# PN532.net
KiCad netlist of a schematic drawn in Altium Designer
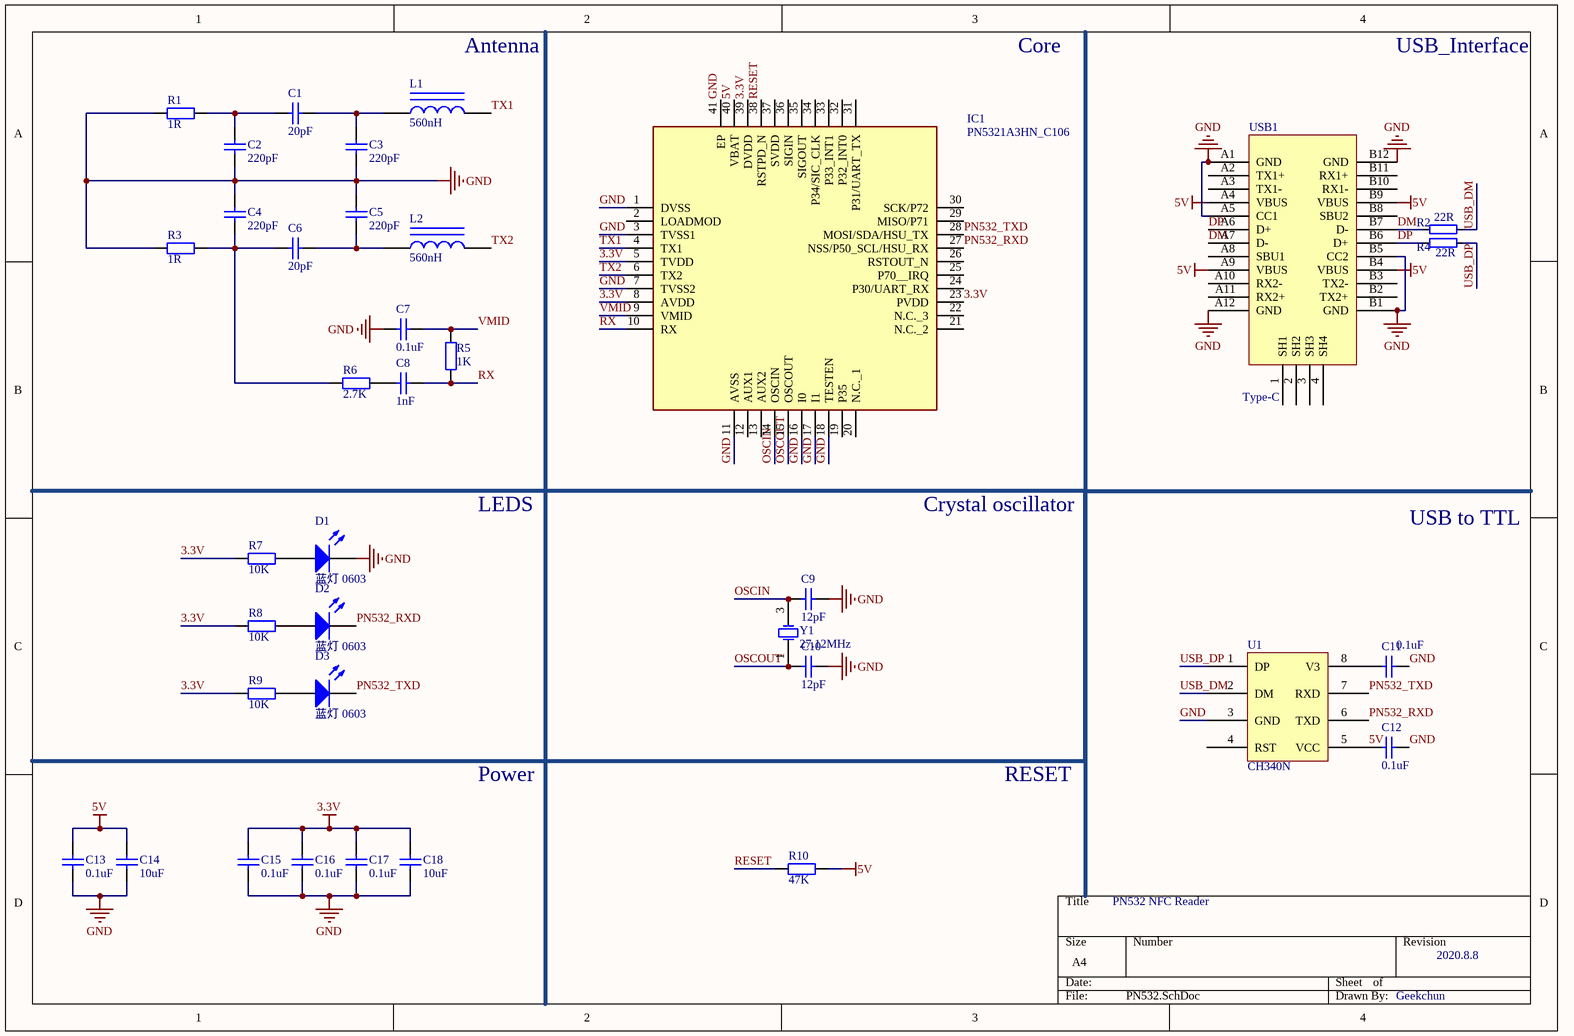
[diagram p0: PN532.SchDoc]

(export (version "E")
  (design (tool "Eeschema 10.0.6"))
  (components
    (comp (ref "C1")
      (value "20pF")
      (footprint "C 0402_L")
      (description "贴片电容")
      (libsource (lib "jialichuang") (part "0402 1.0uF (105) 10% 25V"))
    )
    (comp (ref "C2")
      (value "220pF")
      (footprint "C 0402_L")
      (description "贴片电容")
      (libsource (lib "jialichuang") (part "0402 1.0uF (105) 10% 25V"))
    )
    (comp (ref "C3")
      (value "220pF")
      (footprint "C 0402_L")
      (description "贴片电容")
      (libsource (lib "jialichuang") (part "0402 1.0uF (105) 10% 25V"))
    )
    (comp (ref "C4")
      (value "220pF")
      (footprint "C 0402_L")
      (description "贴片电容")
      (libsource (lib "jialichuang") (part "0402 1.0uF (105) 10% 25V"))
    )
    (comp (ref "C5")
      (value "220pF")
      (footprint "C 0402_L")
      (description "贴片电容")
      (libsource (lib "jialichuang") (part "0402 1.0uF (105) 10% 25V"))
    )
    (comp (ref "C6")
      (value "20pF")
      (footprint "C 0402_L")
      (description "贴片电容")
      (libsource (lib "jialichuang") (part "0402 1.0uF (105) 10% 25V"))
    )
    (comp (ref "C7")
      (value "0.1uF")
      (footprint "C 0402_L")
      (description "贴片电容")
      (libsource (lib "jialichuang") (part "0402 1.0uF (105) 10% 25V"))
    )
    (comp (ref "C8")
      (value "1nF")
      (footprint "C 0402_L")
      (description "贴片电容")
      (libsource (lib "jialichuang") (part "0402 1.0uF (105) 10% 25V"))
    )
    (comp (ref "C9")
      (value "12pF")
      (footprint "C 0402_L")
      (description "贴片电容")
      (libsource (lib "jialichuang") (part "0402 1.0uF (105) 10% 25V"))
    )
    (comp (ref "C10")
      (value "12pF")
      (footprint "C 0402_L")
      (description "贴片电容")
      (libsource (lib "jialichuang") (part "0402 1.0uF (105) 10% 25V"))
    )
    (comp (ref "C11")
      (value "0.1uF")
      (footprint "C 0402_L")
      (description "贴片电容")
      (libsource (lib "jialichuang") (part "0402 1.0uF (105) 10% 25V"))
    )
    (comp (ref "C12")
      (value "0.1uF")
      (footprint "C 0402_L")
      (description "贴片电容")
      (libsource (lib "jialichuang") (part "0402 1.0uF (105) 10% 25V"))
    )
    (comp (ref "C13")
      (value "0.1uF")
      (footprint "C 0402_L")
      (description "贴片电容")
      (libsource (lib "jialichuang") (part "0402 1.0uF (105) 10% 25V"))
    )
    (comp (ref "C14")
      (value "10uF")
      (footprint "C 0402_L")
      (description "贴片电容")
      (libsource (lib "jialichuang") (part "0402 1.0uF (105) 10% 25V"))
    )
    (comp (ref "C15")
      (value "0.1uF")
      (footprint "C 0402_L")
      (description "贴片电容")
      (libsource (lib "jialichuang") (part "0402 1.0uF (105) 10% 25V"))
    )
    (comp (ref "C16")
      (value "0.1uF")
      (footprint "C 0402_L")
      (description "贴片电容")
      (libsource (lib "jialichuang") (part "0402 1.0uF (105) 10% 25V"))
    )
    (comp (ref "C17")
      (value "0.1uF")
      (footprint "C 0402_L")
      (description "贴片电容")
      (libsource (lib "jialichuang") (part "0402 1.0uF (105) 10% 25V"))
    )
    (comp (ref "C18")
      (value "10uF")
      (footprint "C 0402_L")
      (description "贴片电容")
      (libsource (lib "jialichuang") (part "0402 1.0uF (105) 10% 25V"))
    )
    (comp (ref "D1")
      (value "蓝灯 0603")
      (footprint "0603_LED_S1")
      (description "发光二极管")
      (libsource (lib "jialichuang") (part "0603 蓝灯"))
    )
    (comp (ref "D2")
      (value "蓝灯 0603")
      (footprint "0603_LED_S1")
      (description "发光二极管")
      (libsource (lib "jialichuang") (part "0603 蓝灯"))
    )
    (comp (ref "D3")
      (value "蓝灯 0603")
      (footprint "0603_LED_S1")
      (description "发光二极管")
      (libsource (lib "jialichuang") (part "0603 蓝灯"))
    )
    (comp (ref "IC1")
      (value "PN5321A3HN_C106")
      (footprint "QFN40 6X6_L")
      (description "Integrated Circuit")
      (fields
        (field (name "MANUFACTURER_PART_NUMBER") "PN5321A3HN/C106;55")
        (field (name "MOUSER PART NUMBER") "771-PN5321A3HNC106")
      )
      (libsource (lib "SamacSys") (part "PN5321A3HN_C106;55"))
    )
    (comp (ref "L1")
      (value "560nH")
      (footprint "0402_L")
      (description "贴片电感")
      (libsource (lib "jialichuang") (part "0402 12nH  5%"))
    )
    (comp (ref "L2")
      (value "560nH")
      (footprint "0402_L")
      (description "贴片电感")
      (libsource (lib "jialichuang") (part "0402 12nH  5%"))
    )
    (comp (ref "R1")
      (value "1R")
      (footprint "R 0402_L")
      (description "贴片电阻")
      (libsource (lib "jialichuang") (part "0402 1.2KΩ (1201) 1%"))
    )
    (comp (ref "R2") (value "22R") (footprint "R 0402_L") (libsource (lib "电阻") (part "RES")))
    (comp (ref "R3")
      (value "1R")
      (footprint "R 0402_L")
      (description "贴片电阻")
      (libsource (lib "jialichuang") (part "0402 1.2KΩ (1201) 1%"))
    )
    (comp (ref "R4") (value "22R") (footprint "R 0402_L") (libsource (lib "电阻") (part "RES")))
    (comp (ref "R5")
      (value "1K")
      (footprint "R 0402_L")
      (description "贴片电阻")
      (libsource (lib "") (part "0402 1.2KΩ (1201) 1%_1"))
    )
    (comp (ref "R6")
      (value "2.7K")
      (footprint "R 0402_L")
      (description "贴片电阻")
      (libsource (lib "jialichuang") (part "0402 1.2KΩ (1201) 1%"))
    )
    (comp (ref "R7")
      (value "10K")
      (footprint "R 0402_L")
      (description "贴片电阻")
      (libsource (lib "jialichuang") (part "0402 1.2KΩ (1201) 1%"))
    )
    (comp (ref "R8")
      (value "10K")
      (footprint "R 0402_L")
      (description "贴片电阻")
      (libsource (lib "jialichuang") (part "0402 1.2KΩ (1201) 1%"))
    )
    (comp (ref "R9")
      (value "10K")
      (footprint "R 0402_L")
      (description "贴片电阻")
      (libsource (lib "jialichuang") (part "0402 1.2KΩ (1201) 1%"))
    )
    (comp (ref "R10")
      (value "47K")
      (footprint "R 0402_L")
      (description "贴片电阻")
      (libsource (lib "jialichuang") (part "0402 1.2KΩ (1201) 1%"))
    )
    (comp (ref "U1") (value "CH340N") (footprint "SOP8_L") (libsource (lib "PN532") (part "CH340N")))
    (comp (ref "USB1") (value "Type-C") (footprint "usb typec") (libsource (lib "元件") (part "Type-C")))
    (comp (ref "Y1")
      (value "27.12MHz")
      (footprint "OSC 3225-4P")
      (description "贴片晶振")
      (libsource (lib "jialichuang") (part "SMD-3225_4P  12MHZ 20PF 10PPM"))
    )
  )
  (nets
    (net (code "1") (name "/DM") (class "Default")
      (node (ref "R2") (pin "1") (pinfunction "1_1") (pintype "passive"))
      (node (ref "USB1") (pin "A7") (pinfunction "D-_A7") (pintype "passive"))
      (node (ref "USB1") (pin "B7") (pinfunction "D-_B7") (pintype "passive"))
    )
    (net (code "2") (name "/DP") (class "Default")
      (node (ref "R4") (pin "1") (pinfunction "1_1") (pintype "passive"))
      (node (ref "USB1") (pin "A6") (pinfunction "D+_A6") (pintype "passive"))
      (node (ref "USB1") (pin "B6") (pinfunction "D+_B6") (pintype "passive"))
    )
    (net (code "3") (name "/OSCIN") (class "Default")
      (node (ref "C9") (pin "2") (pinfunction "2_2") (pintype "passive"))
      (node (ref "IC1") (pin "14") (pinfunction "OSCIN_14") (pintype "passive"))
      (node (ref "Y1") (pin "3") (pinfunction "OSC2_3") (pintype "passive"))
    )
    (net (code "4") (name "/OSCOUT") (class "Default")
      (node (ref "C10") (pin "2") (pinfunction "2_2") (pintype "passive"))
      (node (ref "IC1") (pin "15") (pinfunction "OSCOUT_15") (pintype "passive"))
      (node (ref "Y1") (pin "1") (pinfunction "OSC1_1") (pintype "passive"))
    )
    (net (code "5") (name "/PN532_RXD") (class "Default")
      (node (ref "D2") (pin "K") (pinfunction "K_K") (pintype "passive"))
      (node (ref "IC1") (pin "27") (pinfunction "NSS/P50_SCL/HSU_RX_27") (pintype "passive"))
      (node (ref "U1") (pin "6") (pinfunction "TXD_6") (pintype "passive"))
    )
    (net (code "6") (name "/PN532_TXD") (class "Default")
      (node (ref "D3") (pin "K") (pinfunction "K_K") (pintype "passive"))
      (node (ref "IC1") (pin "28") (pinfunction "MOSI/SDA/HSU_TX_28") (pintype "passive"))
      (node (ref "U1") (pin "7") (pinfunction "RXD_7") (pintype "passive"))
    )
    (net (code "7") (name "/RESET") (class "Default")
      (node (ref "IC1") (pin "38") (pinfunction "RSTPD_N_38") (pintype "passive"))
      (node (ref "R10") (pin "1") (pinfunction "1_1") (pintype "passive"))
    )
    (net (code "8") (name "/RX") (class "Default")
      (node (ref "C8") (pin "2") (pinfunction "2_2") (pintype "passive"))
      (node (ref "IC1") (pin "10") (pinfunction "RX_10") (pintype "passive"))
      (node (ref "R5") (pin "1") (pinfunction "1_1") (pintype "passive"))
    )
    (net (code "9") (name "/TX1") (class "Default")
      (node (ref "IC1") (pin "4") (pinfunction "TX1_4") (pintype "passive"))
      (node (ref "L1") (pin "2") (pinfunction "2_2") (pintype "passive"))
    )
    (net (code "10") (name "/TX2") (class "Default")
      (node (ref "IC1") (pin "6") (pinfunction "TX2_6") (pintype "passive"))
      (node (ref "L2") (pin "2") (pinfunction "2_2") (pintype "passive"))
    )
    (net (code "11") (name "/USB_DM") (class "Default")
      (node (ref "R2") (pin "2") (pinfunction "2_2") (pintype "passive"))
      (node (ref "U1") (pin "2") (pinfunction "DM_2") (pintype "passive"))
    )
    (net (code "12") (name "/USB_DP") (class "Default")
      (node (ref "R4") (pin "2") (pinfunction "2_2") (pintype "passive"))
      (node (ref "U1") (pin "1") (pinfunction "DP_1") (pintype "passive"))
    )
    (net (code "13") (name "/VMID") (class "Default")
      (node (ref "C7") (pin "2") (pinfunction "2_2") (pintype "passive"))
      (node (ref "IC1") (pin "9") (pinfunction "VMID_9") (pintype "passive"))
      (node (ref "R5") (pin "2") (pinfunction "2_2") (pintype "passive"))
    )
    (net (code "14") (name "3.3V") (class "Default")
      (node (ref "C15") (pin "2") (pinfunction "2_2") (pintype "passive"))
      (node (ref "C16") (pin "2") (pinfunction "2_2") (pintype "passive"))
      (node (ref "C17") (pin "2") (pinfunction "2_2") (pintype "passive"))
      (node (ref "C18") (pin "2") (pinfunction "2_2") (pintype "passive"))
      (node (ref "IC1") (pin "23") (pinfunction "PVDD_23") (pintype "passive"))
      (node (ref "IC1") (pin "39") (pinfunction "DVDD_39") (pintype "passive"))
      (node (ref "IC1") (pin "5") (pinfunction "TVDD_5") (pintype "passive"))
      (node (ref "IC1") (pin "8") (pinfunction "AVDD_8") (pintype "passive"))
      (node (ref "R7") (pin "1") (pinfunction "1_1") (pintype "passive"))
      (node (ref "R8") (pin "1") (pinfunction "1_1") (pintype "passive"))
      (node (ref "R9") (pin "1") (pinfunction "1_1") (pintype "passive"))
    )
    (net (code "15") (name "5V") (class "Default")
      (node (ref "C12") (pin "1") (pinfunction "1_1") (pintype "passive"))
      (node (ref "C13") (pin "2") (pinfunction "2_2") (pintype "passive"))
      (node (ref "C14") (pin "2") (pinfunction "2_2") (pintype "passive"))
      (node (ref "IC1") (pin "40") (pinfunction "VBAT_40") (pintype "passive"))
      (node (ref "R10") (pin "2") (pinfunction "2_2") (pintype "passive"))
      (node (ref "U1") (pin "5") (pinfunction "VCC_5") (pintype "passive"))
      (node (ref "USB1") (pin "A4") (pinfunction "VBUS_A4") (pintype "passive"))
      (node (ref "USB1") (pin "A9") (pinfunction "VBUS_A9") (pintype "passive"))
      (node (ref "USB1") (pin "B4") (pinfunction "VBUS_B4") (pintype "passive"))
      (node (ref "USB1") (pin "B9") (pinfunction "VBUS_B9") (pintype "passive"))
    )
    (net (code "16") (name "GND") (class "Default")
      (node (ref "C10") (pin "1") (pinfunction "1_1") (pintype "passive"))
      (node (ref "C11") (pin "1") (pinfunction "1_1") (pintype "passive"))
      (node (ref "C12") (pin "2") (pinfunction "2_2") (pintype "passive"))
      (node (ref "C13") (pin "1") (pinfunction "1_1") (pintype "passive"))
      (node (ref "C14") (pin "1") (pinfunction "1_1") (pintype "passive"))
      (node (ref "C15") (pin "1") (pinfunction "1_1") (pintype "passive"))
      (node (ref "C16") (pin "1") (pinfunction "1_1") (pintype "passive"))
      (node (ref "C17") (pin "1") (pinfunction "1_1") (pintype "passive"))
      (node (ref "C18") (pin "1") (pinfunction "1_1") (pintype "passive"))
      (node (ref "C2") (pin "2") (pinfunction "2_2") (pintype "passive"))
      (node (ref "C3") (pin "2") (pinfunction "2_2") (pintype "passive"))
      (node (ref "C4") (pin "1") (pinfunction "1_1") (pintype "passive"))
      (node (ref "C5") (pin "1") (pinfunction "1_1") (pintype "passive"))
      (node (ref "C7") (pin "1") (pinfunction "1_1") (pintype "passive"))
      (node (ref "C9") (pin "1") (pinfunction "1_1") (pintype "passive"))
      (node (ref "D1") (pin "K") (pinfunction "K_K") (pintype "passive"))
      (node (ref "IC1") (pin "1") (pinfunction "DVSS_1") (pintype "passive"))
      (node (ref "IC1") (pin "11") (pinfunction "AVSS_11") (pintype "passive"))
      (node (ref "IC1") (pin "16") (pinfunction "I0_16") (pintype "passive"))
      (node (ref "IC1") (pin "17") (pinfunction "I1_17") (pintype "passive"))
      (node (ref "IC1") (pin "18") (pinfunction "TESTEN_18") (pintype "passive"))
      (node (ref "IC1") (pin "3") (pinfunction "TVSS1_3") (pintype "passive"))
      (node (ref "IC1") (pin "41") (pinfunction "EP_41") (pintype "passive"))
      (node (ref "IC1") (pin "7") (pinfunction "TVSS2_7") (pintype "passive"))
      (node (ref "R1") (pin "1") (pinfunction "1_1") (pintype "passive"))
      (node (ref "R3") (pin "1") (pinfunction "1_1") (pintype "passive"))
      (node (ref "U1") (pin "3") (pinfunction "GND_3") (pintype "passive"))
      (node (ref "USB1") (pin "A1") (pinfunction "GND_A1") (pintype "passive"))
      (node (ref "USB1") (pin "A12") (pinfunction "GND_A12") (pintype "passive"))
      (node (ref "USB1") (pin "A5") (pinfunction "CC1_A5") (pintype "passive"))
      (node (ref "USB1") (pin "B1") (pinfunction "GND_B1") (pintype "passive"))
      (node (ref "USB1") (pin "B12") (pinfunction "GND_B12") (pintype "passive"))
      (node (ref "USB1") (pin "B5") (pinfunction "CC2_B5") (pintype "passive"))
    )
    (net (code "17") (name "Net-(C1-Pad1)") (class "Default")
      (node (ref "C1") (pin "1") (pinfunction "1_1") (pintype "passive"))
      (node (ref "C2") (pin "1") (pinfunction "1_1") (pintype "passive"))
      (node (ref "R1") (pin "2") (pinfunction "2_2") (pintype "passive"))
    )
    (net (code "18") (name "Net-(C1-Pad2)") (class "Default")
      (node (ref "C1") (pin "2") (pinfunction "2_2") (pintype "passive"))
      (node (ref "C3") (pin "1") (pinfunction "1_1") (pintype "passive"))
      (node (ref "L1") (pin "1") (pinfunction "1_1") (pintype "passive"))
    )
    (net (code "19") (name "Net-(C4-Pad2)") (class "Default")
      (node (ref "C4") (pin "2") (pinfunction "2_2") (pintype "passive"))
      (node (ref "C6") (pin "1") (pinfunction "1_1") (pintype "passive"))
      (node (ref "R3") (pin "2") (pinfunction "2_2") (pintype "passive"))
      (node (ref "R6") (pin "1") (pinfunction "1_1") (pintype "passive"))
    )
    (net (code "20") (name "Net-(C5-Pad2)") (class "Default")
      (node (ref "C5") (pin "2") (pinfunction "2_2") (pintype "passive"))
      (node (ref "C6") (pin "2") (pinfunction "2_2") (pintype "passive"))
      (node (ref "L2") (pin "1") (pinfunction "1_1") (pintype "passive"))
    )
    (net (code "21") (name "Net-(C8-Pad1)") (class "Default")
      (node (ref "C8") (pin "1") (pinfunction "1_1") (pintype "passive"))
      (node (ref "R6") (pin "2") (pinfunction "2_2") (pintype "passive"))
    )
    (net (code "22") (name "Net-(D1-PadA)") (class "Default")
      (node (ref "D1") (pin "A") (pinfunction "A_A") (pintype "passive"))
      (node (ref "R7") (pin "2") (pinfunction "2_2") (pintype "passive"))
    )
    (net (code "23") (name "Net-(D2-PadA)") (class "Default")
      (node (ref "D2") (pin "A") (pinfunction "A_A") (pintype "passive"))
      (node (ref "R8") (pin "2") (pinfunction "2_2") (pintype "passive"))
    )
    (net (code "24") (name "Net-(D3-PadA)") (class "Default")
      (node (ref "D3") (pin "A") (pinfunction "A_A") (pintype "passive"))
      (node (ref "R9") (pin "2") (pinfunction "2_2") (pintype "passive"))
    )
    (net (code "25") (name "Net-(U1-V3)") (class "Default")
      (node (ref "C11") (pin "2") (pinfunction "2_2") (pintype "passive"))
      (node (ref "U1") (pin "8") (pinfunction "V3_8") (pintype "passive"))
    )
    (net (code "26") (name "unconnected-(IC1-AUX1-Pad12)") (class "Default")
      (node (ref "IC1") (pin "12") (pinfunction "AUX1_12") (pintype "passive"))
    )
    (net (code "27") (name "unconnected-(IC1-AUX2-Pad13)") (class "Default")
      (node (ref "IC1") (pin "13") (pinfunction "AUX2_13") (pintype "passive"))
    )
    (net (code "28") (name "unconnected-(IC1-LOADMOD-Pad2)") (class "Default")
      (node (ref "IC1") (pin "2") (pinfunction "LOADMOD_2") (pintype "passive"))
    )
    (net (code "29") (name "unconnected-(IC1-MISO{slash}P71-Pad29)") (class "Default")
      (node (ref "IC1") (pin "29") (pinfunction "MISO/P71_29") (pintype "passive"))
    )
    (net (code "30") (name "unconnected-(IC1-N.C._1-Pad20)") (class "Default")
      (node (ref "IC1") (pin "20") (pinfunction "N.C._1_20") (pintype "passive"))
    )
    (net (code "31") (name "unconnected-(IC1-N.C._2-Pad21)") (class "Default")
      (node (ref "IC1") (pin "21") (pinfunction "N.C._2_21") (pintype "passive"))
    )
    (net (code "32") (name "unconnected-(IC1-N.C._3-Pad22)") (class "Default")
      (node (ref "IC1") (pin "22") (pinfunction "N.C._3_22") (pintype "passive"))
    )
    (net (code "33") (name "unconnected-(IC1-P30{slash}UART_RX-Pad24)") (class "Default")
      (node (ref "IC1") (pin "24") (pinfunction "P30/UART_RX_24") (pintype "passive"))
    )
    (net (code "34") (name "unconnected-(IC1-P31{slash}UART_TX-Pad31)") (class "Default")
      (node (ref "IC1") (pin "31") (pinfunction "P31/UART_TX_31") (pintype "passive"))
    )
    (net (code "35") (name "unconnected-(IC1-P32_INT0-Pad32)") (class "Default")
      (node (ref "IC1") (pin "32") (pinfunction "P32_INT0_32") (pintype "passive"))
    )
    (net (code "36") (name "unconnected-(IC1-P33_INT1-Pad33)") (class "Default")
      (node (ref "IC1") (pin "33") (pinfunction "P33_INT1_33") (pintype "passive"))
    )
    (net (code "37") (name "unconnected-(IC1-P34{slash}SIC_CLK-Pad34)") (class "Default")
      (node (ref "IC1") (pin "34") (pinfunction "P34/SIC_CLK_34") (pintype "passive"))
    )
    (net (code "38") (name "unconnected-(IC1-P35-Pad19)") (class "Default")
      (node (ref "IC1") (pin "19") (pinfunction "P35_19") (pintype "passive"))
    )
    (net (code "39") (name "unconnected-(IC1-P70__IRQ-Pad25)") (class "Default")
      (node (ref "IC1") (pin "25") (pinfunction "P70__IRQ_25") (pintype "passive"))
    )
    (net (code "40") (name "unconnected-(IC1-RSTOUT_N-Pad26)") (class "Default")
      (node (ref "IC1") (pin "26") (pinfunction "RSTOUT_N_26") (pintype "passive"))
    )
    (net (code "41") (name "unconnected-(IC1-SCK{slash}P72-Pad30)") (class "Default")
      (node (ref "IC1") (pin "30") (pinfunction "SCK/P72_30") (pintype "passive"))
    )
    (net (code "42") (name "unconnected-(IC1-SIGIN-Pad36)") (class "Default")
      (node (ref "IC1") (pin "36") (pinfunction "SIGIN_36") (pintype "passive"))
    )
    (net (code "43") (name "unconnected-(IC1-SIGOUT-Pad35)") (class "Default")
      (node (ref "IC1") (pin "35") (pinfunction "SIGOUT_35") (pintype "passive"))
    )
    (net (code "44") (name "unconnected-(IC1-SVDD-Pad37)") (class "Default")
      (node (ref "IC1") (pin "37") (pinfunction "SVDD_37") (pintype "passive"))
    )
    (net (code "45") (name "unconnected-(U1-RST-Pad4)") (class "Default")
      (node (ref "U1") (pin "4") (pinfunction "RST_4") (pintype "passive"))
    )
    (net (code "46") (name "unconnected-(USB1-RX1+-PadB11)") (class "Default")
      (node (ref "USB1") (pin "B11") (pinfunction "RX1+_B11") (pintype "passive"))
    )
    (net (code "47") (name "unconnected-(USB1-RX1--PadB10)") (class "Default")
      (node (ref "USB1") (pin "B10") (pinfunction "RX1-_B10") (pintype "passive"))
    )
    (net (code "48") (name "unconnected-(USB1-RX2+-PadA11)") (class "Default")
      (node (ref "USB1") (pin "A11") (pinfunction "RX2+_A11") (pintype "passive"))
    )
    (net (code "49") (name "unconnected-(USB1-RX2--PadA10)") (class "Default")
      (node (ref "USB1") (pin "A10") (pinfunction "RX2-_A10") (pintype "passive"))
    )
    (net (code "50") (name "unconnected-(USB1-SBU1-PadA8)") (class "Default")
      (node (ref "USB1") (pin "A8") (pinfunction "SBU1_A8") (pintype "passive"))
    )
    (net (code "51") (name "unconnected-(USB1-SBU2-PadB8)") (class "Default")
      (node (ref "USB1") (pin "B8") (pinfunction "SBU2_B8") (pintype "passive"))
    )
    (net (code "52") (name "unconnected-(USB1-SH1-Pad1)") (class "Default")
      (node (ref "USB1") (pin "1") (pinfunction "SH1_1") (pintype "passive"))
    )
    (net (code "53") (name "unconnected-(USB1-SH2-Pad2)") (class "Default")
      (node (ref "USB1") (pin "2") (pinfunction "SH2_2") (pintype "passive"))
    )
    (net (code "54") (name "unconnected-(USB1-SH3-Pad3)") (class "Default")
      (node (ref "USB1") (pin "3") (pinfunction "SH3_3") (pintype "passive"))
    )
    (net (code "55") (name "unconnected-(USB1-SH4-Pad4)") (class "Default")
      (node (ref "USB1") (pin "4") (pinfunction "SH4_4") (pintype "passive"))
    )
    (net (code "56") (name "unconnected-(USB1-TX1+-PadA2)") (class "Default")
      (node (ref "USB1") (pin "A2") (pinfunction "TX1+_A2") (pintype "passive"))
    )
    (net (code "57") (name "unconnected-(USB1-TX1--PadA3)") (class "Default")
      (node (ref "USB1") (pin "A3") (pinfunction "TX1-_A3") (pintype "passive"))
    )
    (net (code "58") (name "unconnected-(USB1-TX2+-PadB2)") (class "Default")
      (node (ref "USB1") (pin "B2") (pinfunction "TX2+_B2") (pintype "passive"))
    )
    (net (code "59") (name "unconnected-(USB1-TX2--PadB3)") (class "Default")
      (node (ref "USB1") (pin "B3") (pinfunction "TX2-_B3") (pintype "passive"))
    )
  )
)
